# EEPROM.net
KiCad netlist of a schematic drawn in Altium Designer
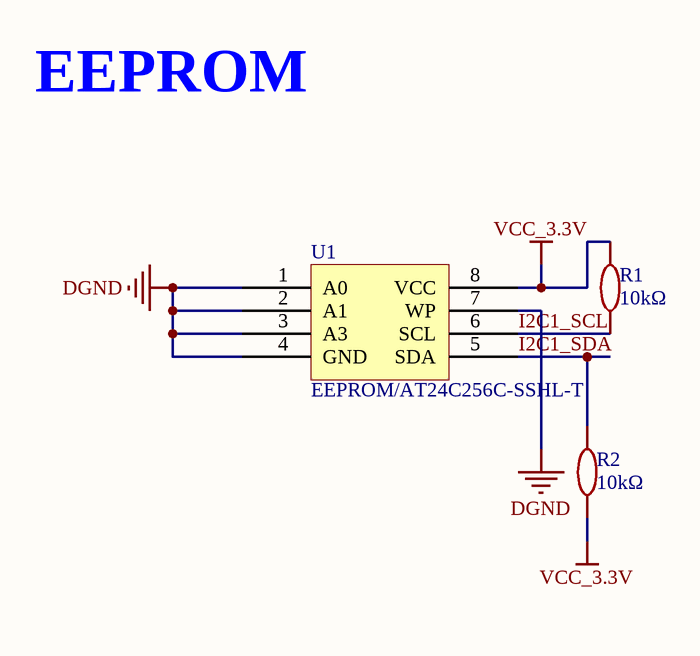
[diagram p0: EEPROM.SchDoc]

(export (version "E")
  (design (tool "Eeschema 10.0.6"))
  (components
    (comp (ref "R1")
      (value "10kΩ")
      (footprint "R0402")
      (description "电阻类型:厚膜电阻;阻值:10kΩ;精度:±1%;功率:100mW;最大工作电压:75V;温度系数:±100ppm/℃;")
      (libsource (lib "XG_DW_POCT_2K10LED_3") (part "10kΩ,R0402"))
    )
    (comp (ref "R2")
      (value "10kΩ")
      (footprint "R0402")
      (description "电阻类型:厚膜电阻;阻值:10kΩ;精度:±1%;功率:100mW;最大工作电压:75V;温度系数:±100ppm/℃;")
      (libsource (lib "XG_DW_POCT_2K10LED_3") (part "10kΩ,R0402"))
    )
    (comp (ref "U1")
      (value "EEPROM/AT24C256C-SSHL-T")
      (footprint "SOIC-8_150mil")
      (description "EEPROM")
      (libsource (lib "XG_DW_POCT_2K10LED_3") (part "EEPROM/AT24C256C-SSHL-T_[C6482]"))
    )
  )
  (nets
    (net (code "1") (name "/I2C1_SCL") (class "Default")
      (node (ref "R1") (pin "1") (pinfunction "1_1") (pintype "passive"))
      (node (ref "U1") (pin "6") (pinfunction "SCL_6") (pintype "passive"))
    )
    (net (code "2") (name "/I2C1_SDA") (class "Default")
      (node (ref "R2") (pin "2") (pinfunction "2_2") (pintype "passive"))
      (node (ref "U1") (pin "5") (pinfunction "SDA_5") (pintype "passive"))
    )
    (net (code "3") (name "DGND") (class "Default")
      (node (ref "U1") (pin "1") (pinfunction "A0_1") (pintype "passive"))
      (node (ref "U1") (pin "2") (pinfunction "A1_2") (pintype "passive"))
      (node (ref "U1") (pin "3") (pinfunction "A3_3") (pintype "passive"))
      (node (ref "U1") (pin "4") (pinfunction "GND_4") (pintype "passive"))
      (node (ref "U1") (pin "7") (pinfunction "WP_7") (pintype "passive"))
    )
    (net (code "4") (name "VCC_3.3V") (class "Default")
      (node (ref "R1") (pin "2") (pinfunction "2_2") (pintype "passive"))
      (node (ref "R2") (pin "1") (pinfunction "1_1") (pintype "passive"))
      (node (ref "U1") (pin "8") (pinfunction "VCC_8") (pintype "passive"))
    )
  )
)
